# Sheet4.net
KiCad netlist of a schematic drawn in Altium Designer
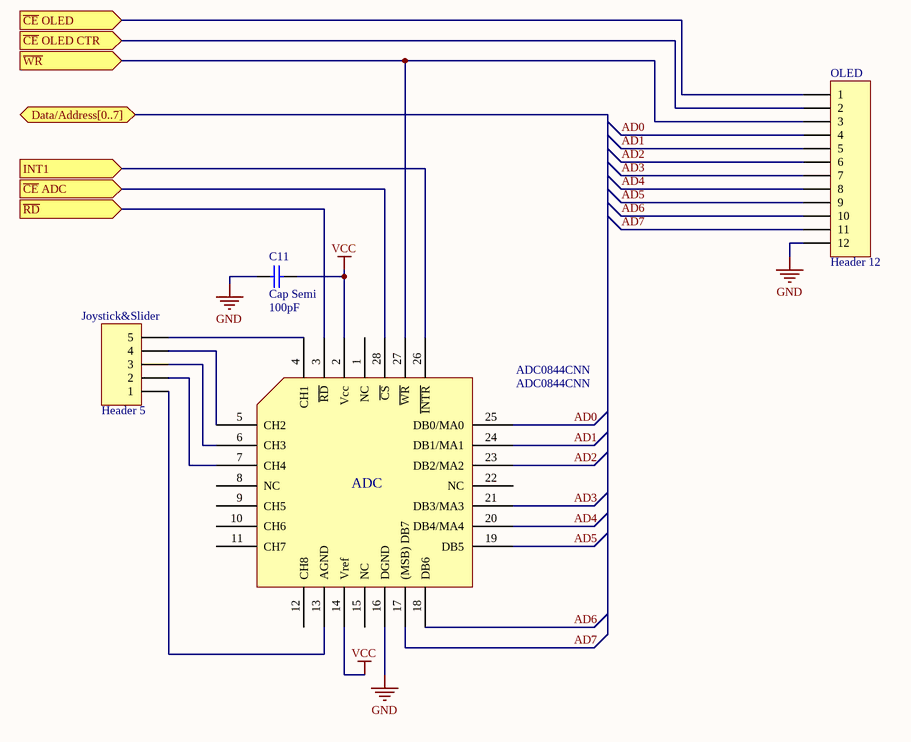
[diagram p0: Sheet4.SchDoc]

(export (version "E")
  (design (tool "Eeschema 10.0.6"))
  (components
    (comp (ref "ADC0844CNN")
      (value "ADC0844CNN")
      (footprint "ADC0844CNN PLCC 28-PIN")
      (description "ADC - Analogue to Digital Converter")
      (libsource (lib "IIDKLib") (part "ADC0844CNN"))
    )
    (comp (ref "C11")
      (value "Cap Semi")
      (footprint "C1210")
      (description "Capacitor (Semiconductor SIM Model)")
      (fields (field (name "ALTIUM_VALUE") "100pF") (field (name "PUBLISHER") "Altium Limited"))
      (libsource (lib "Miscellaneous Devices") (part "Cap Semi"))
    )
    (comp (ref "Joystick&Slider")
      (value "Header 5")
      (footprint "HDR1X5")
      (description "Header, 5-Pin")
      (fields (field (name "PUBLISHER") "Altium Limited"))
      (libsource (lib "Miscellaneous Connectors") (part "Header 5"))
    )
    (comp (ref "OLED")
      (value "Header 12")
      (footprint "HDR1X12")
      (description "Header, 12-Pin")
      (fields (field (name "PUBLISHER") "Altium Limited"))
      (libsource (lib "Miscellaneous Connectors") (part "Header 12"))
    )
  )
  (nets
    (net (code "9") (name "/AD0") (class "Default")
      (node (ref "ADC0844CNN") (pin "25") (pinfunction "DB0/MA0_25") (pintype "passive"))
      (node (ref "OLED") (pin "4") (pinfunction "4_4") (pintype "passive"))
    )
    (net (code "10") (name "/AD1") (class "Default")
      (node (ref "ADC0844CNN") (pin "24") (pinfunction "DB1/MA1_24") (pintype "passive"))
      (node (ref "OLED") (pin "5") (pinfunction "5_5") (pintype "passive"))
    )
    (net (code "11") (name "/AD2") (class "Default")
      (node (ref "ADC0844CNN") (pin "23") (pinfunction "DB2/MA2_23") (pintype "passive"))
      (node (ref "OLED") (pin "6") (pinfunction "6_6") (pintype "passive"))
    )
    (net (code "12") (name "/AD3") (class "Default")
      (node (ref "ADC0844CNN") (pin "21") (pinfunction "DB3/MA3_21") (pintype "passive"))
      (node (ref "OLED") (pin "7") (pinfunction "7_7") (pintype "passive"))
    )
    (net (code "13") (name "/AD4") (class "Default")
      (node (ref "ADC0844CNN") (pin "20") (pinfunction "DB4/MA4_20") (pintype "passive"))
      (node (ref "OLED") (pin "8") (pinfunction "8_8") (pintype "passive"))
    )
    (net (code "14") (name "/AD5") (class "Default")
      (node (ref "ADC0844CNN") (pin "19") (pinfunction "DB5_19") (pintype "passive"))
      (node (ref "OLED") (pin "9") (pinfunction "9_9") (pintype "passive"))
    )
    (net (code "15") (name "/AD6") (class "Default")
      (node (ref "ADC0844CNN") (pin "18") (pinfunction "DB6_18") (pintype "passive"))
      (node (ref "OLED") (pin "10") (pinfunction "10_10") (pintype "passive"))
    )
    (net (code "16") (name "/AD7") (class "Default")
      (node (ref "ADC0844CNN") (pin "17") (pinfunction "(MSB)_DB7_17") (pintype "passive"))
      (node (ref "OLED") (pin "11") (pinfunction "11_11") (pintype "passive"))
    )
    (net (code "18") (name "/INT1") (class "Default")
      (node (ref "ADC0844CNN") (pin "26") (pinfunction "~{INTR}_26") (pintype "passive"))
    )
    (net (code "19") (name "/~{CE} ADC") (class "Default")
      (node (ref "ADC0844CNN") (pin "28") (pinfunction "~{CS}_28") (pintype "passive"))
    )
    (net (code "20") (name "/~{CE} OLED") (class "Default")
      (node (ref "OLED") (pin "1") (pinfunction "1_1") (pintype "passive"))
    )
    (net (code "21") (name "/~{CE} OLED CTR") (class "Default")
      (node (ref "OLED") (pin "2") (pinfunction "2_2") (pintype "passive"))
    )
    (net (code "22") (name "/~{RD}") (class "Default")
      (node (ref "ADC0844CNN") (pin "3") (pinfunction "~{RD}_3") (pintype "passive"))
    )
    (net (code "23") (name "/~{WR}") (class "Default")
      (node (ref "ADC0844CNN") (pin "27") (pinfunction "~{WR}_27") (pintype "passive"))
      (node (ref "OLED") (pin "3") (pinfunction "3_3") (pintype "passive"))
    )
    (net (code "24") (name "GND") (class "Default")
      (node (ref "ADC0844CNN") (pin "16") (pinfunction "DGND_16") (pintype "power_in"))
      (node (ref "C11") (pin "2") (pinfunction "2_2") (pintype "passive"))
      (node (ref "OLED") (pin "12") (pinfunction "12_12") (pintype "passive"))
    )
    (net (code "25") (name "Net-(ADC0844CNN-AGND)") (class "Default")
      (node (ref "ADC0844CNN") (pin "13") (pinfunction "AGND_13") (pintype "power_in"))
      (node (ref "Joystick&Slider") (pin "1") (pinfunction "1_1") (pintype "passive"))
    )
    (net (code "26") (name "Net-(ADC0844CNN-CH1)") (class "Default")
      (node (ref "ADC0844CNN") (pin "4") (pinfunction "CH1_4") (pintype "passive"))
      (node (ref "Joystick&Slider") (pin "5") (pinfunction "5_5") (pintype "passive"))
    )
    (net (code "27") (name "Net-(ADC0844CNN-CH2)") (class "Default")
      (node (ref "ADC0844CNN") (pin "5") (pinfunction "CH2_5") (pintype "passive"))
      (node (ref "Joystick&Slider") (pin "4") (pinfunction "4_4") (pintype "passive"))
    )
    (net (code "28") (name "Net-(ADC0844CNN-CH3)") (class "Default")
      (node (ref "ADC0844CNN") (pin "6") (pinfunction "CH3_6") (pintype "passive"))
      (node (ref "Joystick&Slider") (pin "3") (pinfunction "3_3") (pintype "passive"))
    )
    (net (code "29") (name "Net-(ADC0844CNN-CH4)") (class "Default")
      (node (ref "ADC0844CNN") (pin "7") (pinfunction "CH4_7") (pintype "passive"))
      (node (ref "Joystick&Slider") (pin "2") (pinfunction "2_2") (pintype "passive"))
    )
    (net (code "30") (name "VCC") (class "Default")
      (node (ref "ADC0844CNN") (pin "14") (pinfunction "Vref_14") (pintype "passive"))
      (node (ref "ADC0844CNN") (pin "2") (pinfunction "Vcc_2") (pintype "passive"))
      (node (ref "C11") (pin "1") (pinfunction "1_1") (pintype "passive"))
    )
    (net (code "31") (name "unconnected-(ADC0844CNN-CH5-Pad9)") (class "Default")
      (node (ref "ADC0844CNN") (pin "9") (pinfunction "CH5_9") (pintype "passive"))
    )
    (net (code "32") (name "unconnected-(ADC0844CNN-CH6-Pad10)") (class "Default")
      (node (ref "ADC0844CNN") (pin "10") (pinfunction "CH6_10") (pintype "passive"))
    )
    (net (code "33") (name "unconnected-(ADC0844CNN-CH7-Pad11)") (class "Default")
      (node (ref "ADC0844CNN") (pin "11") (pinfunction "CH7_11") (pintype "passive"))
    )
    (net (code "34") (name "unconnected-(ADC0844CNN-CH8-Pad12)") (class "Default")
      (node (ref "ADC0844CNN") (pin "12") (pinfunction "CH8_12") (pintype "passive"))
    )
    (net (code "35") (name "unconnected-(ADC0844CNN-NC-Pad1)") (class "Default")
      (node (ref "ADC0844CNN") (pin "1") (pinfunction "NC_1") (pintype "passive"))
    )
    (net (code "36") (name "unconnected-(ADC0844CNN-NC-Pad8)") (class "Default")
      (node (ref "ADC0844CNN") (pin "8") (pinfunction "NC_8") (pintype "passive"))
    )
    (net (code "37") (name "unconnected-(ADC0844CNN-NC-Pad15)") (class "Default")
      (node (ref "ADC0844CNN") (pin "15") (pinfunction "NC_15") (pintype "passive"))
    )
    (net (code "38") (name "unconnected-(ADC0844CNN-NC-Pad22)") (class "Default")
      (node (ref "ADC0844CNN") (pin "22") (pinfunction "NC_22") (pintype "passive"))
    )
  )
)
